# Thermocouples.net
KiCad netlist of a schematic drawn in Altium Designer
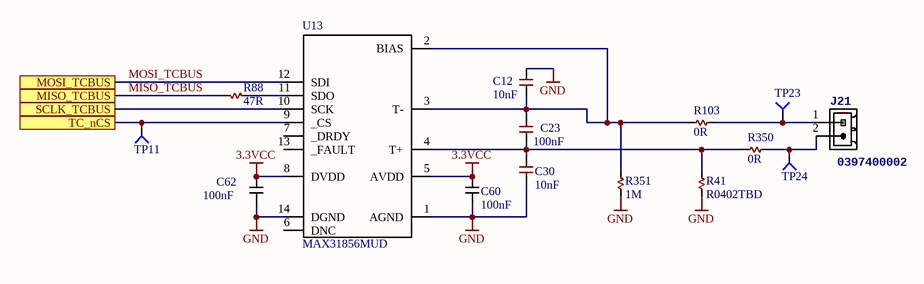
[diagram p0: Thermocouples.SchDoc]

(export (version "E")
  (design (tool "Eeschema 10.0.6"))
  (components
    (comp (ref "C12")
      (value "10nF")
      (footprint "C0402")
      (description "CAP CER 10nF 50V X7R 0402")
      (fields (field (name "TOLERANCE") "5%") (field (name "MANUFACTURER") "Murata"))
      (libsource (lib "Capacitors") (part "10nF 0402 50V X7R"))
    )
    (comp (ref "C23")
      (value "100nF")
      (footprint "C0603")
      (description "CAP CER 0603 100nF 50V 10% X7R")
      (fields (field (name "MANUFACTURER") "Kemet") (field (name "PART") "C0603C104K5RACTU"))
      (libsource (lib "Capacitors") (part "100nF 0603 50V X7R"))
    )
    (comp (ref "C30")
      (value "10nF")
      (footprint "C0402")
      (description "CAP CER 10nF 50V X7R 0402")
      (fields (field (name "TOLERANCE") "5%") (field (name "MANUFACTURER") "Murata"))
      (libsource (lib "Capacitors") (part "10nF 0402 50V X7R"))
    )
    (comp (ref "C60")
      (value "100nF")
      (footprint "C0201 Large Pads")
      (description "CAP CER 0.1UF 6.3V 10% X5R 0201")
      (fields (field (name "MANUFACTURER") "Samsung") (field (name "TOLERANCE") "10%"))
      (libsource (lib "Capacitors") (part "100nF 6.3V X5R 0201"))
    )
    (comp (ref "C62")
      (value "100nF")
      (footprint "C0201 Large Pads")
      (description "CAP CER 0.1UF 6.3V 10% X5R 0201")
      (fields (field (name "MANUFACTURER") "Samsung") (field (name "TOLERANCE") "10%"))
      (libsource (lib "Capacitors") (part "100nF 6.3V X5R 0201"))
    )
    (comp (ref "J21")
      (value "0397400002")
      (footprint "0397400002")
      (description "TERM BLK 2P SIDE ENT 3.81MM PCB")
      (fields (field (name "MANUFACTURER") "Molex") (field (name "TOLERANCE") "NA"))
      (libsource (lib "Connectors") (part "0397400002"))
    )
    (comp (ref "R41")
      (value "R0402TBD")
      (footprint "R0402")
      (description "Resistor")
      (libsource (lib "Resistors") (part "R0402TBD"))
    )
    (comp (ref "R88")
      (value "47R")
      (footprint "R0402")
      (description "RES 47 OHM 1% 1/16W 0402")
      (fields (field (name "MANUFACTURER") "Vishay Dale") (field (name "TOLERANCE") "+/- 1%"))
      (libsource (lib "Resistors") (part "47R 1% 0402"))
    )
    (comp (ref "R103")
      (value "0R")
      (footprint "R0402")
      (description "RES SMD 0.0OHM JUMPER 1/10W 0402")
      (fields (field (name "MANUFACTURER") "Panasonic") (field (name "TOLERANCE") "1%"))
      (libsource (lib "Resistors") (part "0R 0402"))
    )
    (comp (ref "R350")
      (value "0R")
      (footprint "R0402")
      (description "RES SMD 0.0OHM JUMPER 1/10W 0402")
      (fields (field (name "MANUFACTURER") "Panasonic") (field (name "TOLERANCE") "1%"))
      (libsource (lib "Resistors") (part "0R 0402"))
    )
    (comp (ref "R351")
      (value "1M")
      (footprint "Passives:R0402")
      (description "RES 0402 1M 100mW 5%")
      (fields (field (name "MANUFACTURER") "Panasonic") (field (name "PART") "ERJ2GEJ105X"))
      (libsource (lib "Resistors") (part "1M 5% 0402"))
    )
    (comp (ref "TP11")
      (value "TP4")
      (footprint "TP-2")
      (description "Socket")
      (fields (field (name "PART") "NOTAPART-Testpoint"))
      (libsource (lib "Archim") (part "Socket"))
    )
    (comp (ref "TP23")
      (value "TP4")
      (footprint "TP-2")
      (description "Socket")
      (fields (field (name "PART") "NOTAPART-Testpoint"))
      (libsource (lib "Archim") (part "Socket"))
    )
    (comp (ref "TP24")
      (value "TP4")
      (footprint "TP-2")
      (description "Socket")
      (fields (field (name "PART") "NOTAPART-Testpoint"))
      (libsource (lib "Archim") (part "Socket"))
    )
    (comp (ref "U13")
      (value "MAX31856MUD")
      (footprint "TSSOP-14L 65P640X110")
      (description "IC CONV THERMOCOUPLE 14TSSOP")
      (fields (field (name "MANUFACTURER") "Maxim") (field (name "VOLTAGE") "3.3V"))
      (libsource (lib "ICs-Analog") (part "MAX31856"))
    )
  )
  (nets
    (net (code "1") (name "/MISO_TCBUS") (class "Default")
      (node (ref "R88") (pin "2") (pinfunction "2_2") (pintype "passive"))
    )
    (net (code "2") (name "/MOSI_TCBUS") (class "Default")
      (node (ref "U13") (pin "12") (pinfunction "SDI_12") (pintype "power_in"))
    )
    (net (code "3") (name "/SCLK_TCBUS") (class "Default")
      (node (ref "U13") (pin "10") (pinfunction "SCK_10") (pintype "power_in"))
    )
    (net (code "4") (name "/TC_nCS") (class "Default")
      (node (ref "TP11") (pin "1") (pinfunction "1_1") (pintype "passive"))
      (node (ref "U13") (pin "9") (pinfunction "_CS_9") (pintype "power_in"))
    )
    (net (code "5") (name "3.3VCC") (class "Default")
      (node (ref "C60") (pin "2") (pinfunction "2_2") (pintype "passive"))
      (node (ref "C62") (pin "2") (pinfunction "2_2") (pintype "passive"))
      (node (ref "U13") (pin "5") (pinfunction "AVDD_5") (pintype "passive"))
      (node (ref "U13") (pin "8") (pinfunction "DVDD_8") (pintype "passive"))
    )
    (net (code "6") (name "GND") (class "Default")
      (node (ref "C12") (pin "2") (pinfunction "2_2") (pintype "passive"))
      (node (ref "C30") (pin "1") (pinfunction "1_1") (pintype "passive"))
      (node (ref "C60") (pin "1") (pinfunction "1_1") (pintype "passive"))
      (node (ref "C62") (pin "1") (pinfunction "1_1") (pintype "passive"))
      (node (ref "R351") (pin "2") (pinfunction "2_2") (pintype "passive"))
      (node (ref "R41") (pin "1") (pinfunction "1_1") (pintype "passive"))
      (node (ref "U13") (pin "1") (pinfunction "AGND_1") (pintype "passive"))
      (node (ref "U13") (pin "14") (pinfunction "DGND_14") (pintype "power_in"))
    )
    (net (code "7") (name "Net-(J21-Pad1)") (class "Default")
      (node (ref "J21") (pin "1") (pinfunction "1_1") (pintype "passive"))
      (node (ref "R103") (pin "2") (pinfunction "2_2") (pintype "passive"))
      (node (ref "TP23") (pin "1") (pinfunction "1_1") (pintype "passive"))
    )
    (net (code "8") (name "Net-(J21-Pad2)") (class "Default")
      (node (ref "J21") (pin "2") (pinfunction "2_2") (pintype "passive"))
      (node (ref "R350") (pin "2") (pinfunction "2_2") (pintype "passive"))
      (node (ref "TP24") (pin "1") (pinfunction "1_1") (pintype "passive"))
    )
    (net (code "9") (name "Net-(U13-BIAS)") (class "Default")
      (node (ref "C12") (pin "1") (pinfunction "1_1") (pintype "passive"))
      (node (ref "C23") (pin "2") (pinfunction "2_2") (pintype "passive"))
      (node (ref "R103") (pin "1") (pinfunction "1_1") (pintype "passive"))
      (node (ref "R351") (pin "1") (pinfunction "1_1") (pintype "passive"))
      (node (ref "U13") (pin "2") (pinfunction "BIAS_2") (pintype "passive"))
      (node (ref "U13") (pin "3") (pinfunction "T-_3") (pintype "passive"))
    )
    (net (code "10") (name "Net-(U13-SDO)") (class "Default")
      (node (ref "R88") (pin "1") (pinfunction "1_1") (pintype "passive"))
      (node (ref "U13") (pin "11") (pinfunction "SDO_11") (pintype "power_in"))
    )
    (net (code "11") (name "Net-(U13-T+)") (class "Default")
      (node (ref "C23") (pin "1") (pinfunction "1_1") (pintype "passive"))
      (node (ref "C30") (pin "2") (pinfunction "2_2") (pintype "passive"))
      (node (ref "R350") (pin "1") (pinfunction "1_1") (pintype "passive"))
      (node (ref "R41") (pin "2") (pinfunction "2_2") (pintype "passive"))
      (node (ref "U13") (pin "4") (pinfunction "T+_4") (pintype "passive"))
    )
    (net (code "12") (name "unconnected-(U13-DNC-Pad6)") (class "Default")
      (node (ref "U13") (pin "6") (pinfunction "DNC_6") (pintype "passive"))
    )
    (net (code "13") (name "unconnected-(U13-_DRDY-Pad7)") (class "Default")
      (node (ref "U13") (pin "7") (pinfunction "_DRDY_7") (pintype "passive"))
    )
    (net (code "14") (name "unconnected-(U13-_FAULT-Pad13)") (class "Default")
      (node (ref "U13") (pin "13") (pinfunction "_FAULT_13") (pintype "power_in"))
    )
  )
)
